# design.net
KiCad netlist of a schematic drawn in Altium Designer
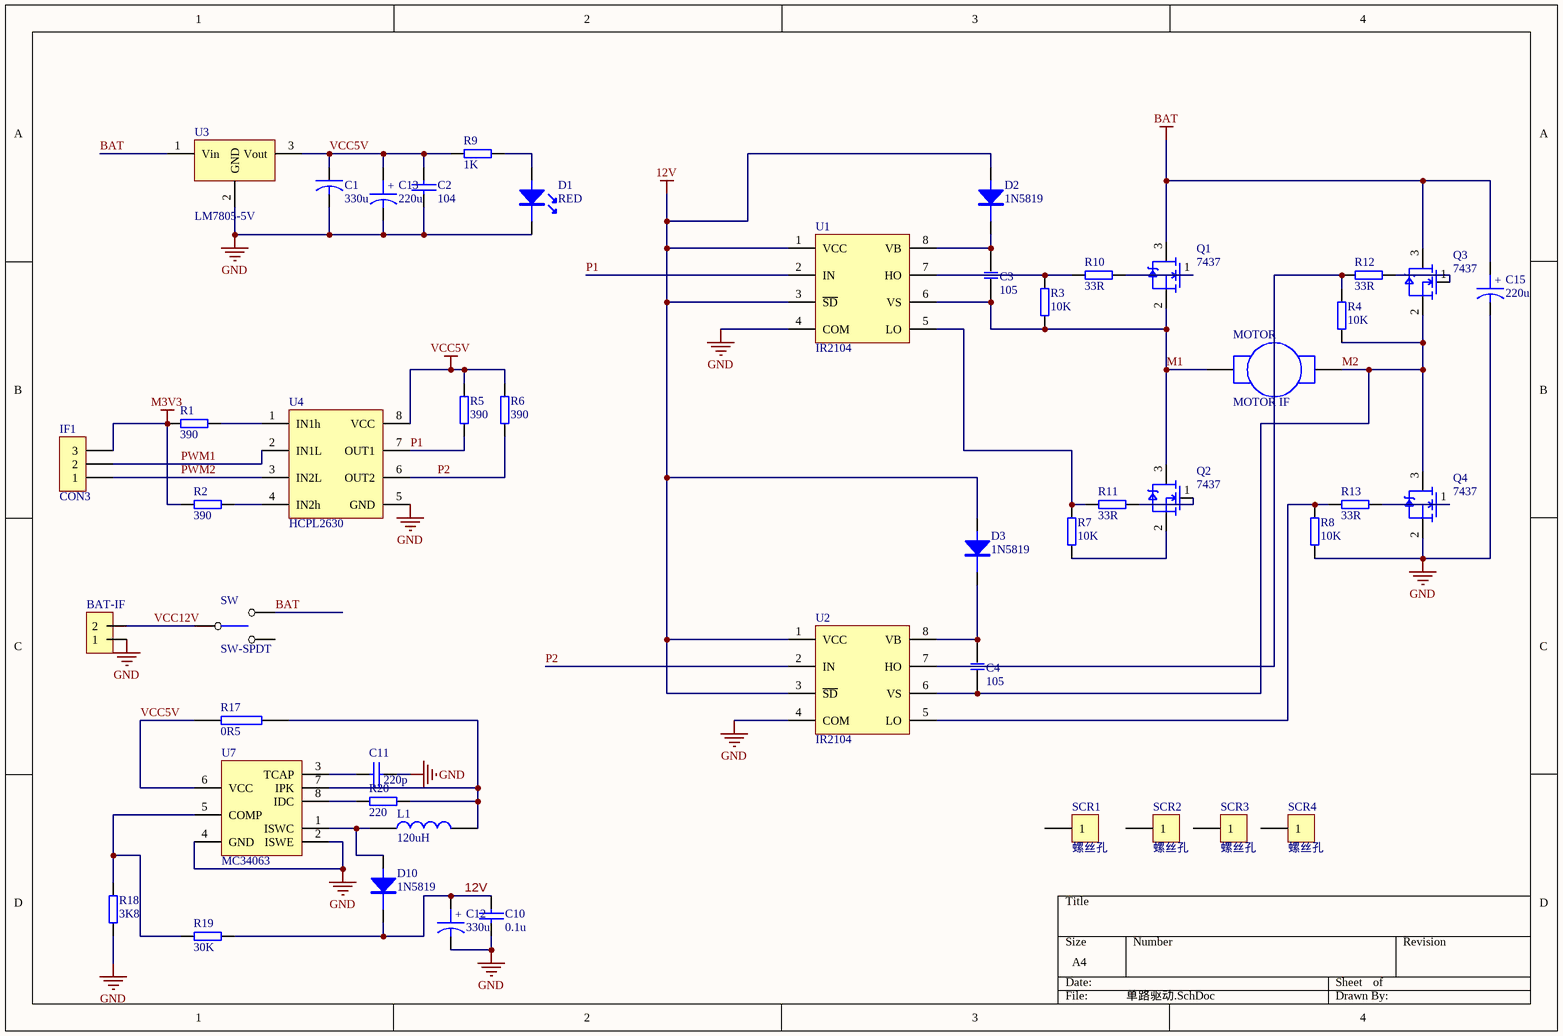
[diagram p0: 单路驱动.SchDoc]

(export (version "E")
  (design (tool "Eeschema 10.0.6"))
  (components
    (comp (ref "BAT-IF")
      (value "LQ_PIN2")
      (footprint "LQ_PIN2")
      (description "Jumper")
      (libsource (lib "LQ_MOSFET光隔全桥双路驱动加强版Vh") (part "LQ_PIN2"))
    )
    (comp (ref "C1")
      (value "330u")
      (footprint "LQ_7343D")
      (description "Capacitor")
      (libsource (lib "LQ_MOSFET光隔全桥双路驱动加强版Vh") (part "CAPACITOR"))
    )
    (comp (ref "C2")
      (value "104")
      (footprint "LQ_0603")
      (description "Capacitor")
      (libsource (lib "LQ_MOSFET光隔全桥双路驱动加强版Vh") (part "CAP"))
    )
    (comp (ref "C3")
      (value "105")
      (footprint "LQ_0603")
      (description "CAP")
      (libsource (lib "LQ_MOSFET光隔全桥双路驱动加强版Vh") (part "LQ_CAP"))
    )
    (comp (ref "C4")
      (value "105")
      (footprint "LQ_0603")
      (description "CAP")
      (libsource (lib "LQ_MOSFET光隔全桥双路驱动加强版Vh") (part "LQ_CAP"))
    )
    (comp (ref "C10")
      (value "0.1u")
      (footprint "LQ_0603")
      (description "Capacitor")
      (libsource (lib "LQ_MOSFET光隔全桥双路驱动加强版Vh") (part "CAP"))
    )
    (comp (ref "C11")
      (value "220p")
      (footprint "LQ_0603")
      (description "Capacitor")
      (libsource (lib "LQ_MOSFET光隔全桥双路驱动加强版Vh") (part "CAP"))
    )
    (comp (ref "C12")
      (value "330u")
      (footprint "LQ_220U16V")
      (description "10u")
      (libsource (lib "LQ_MOSFET光隔全桥双路驱动加强版Vh") (part "LQ_CAP_POL"))
    )
    (comp (ref "C13")
      (value "220u")
      (footprint "LQ_220U16V")
      (description "10u")
      (libsource (lib "LQ_MOSFET光隔全桥双路驱动加强版Vh") (part "LQ_CAP_POL"))
    )
    (comp (ref "C15")
      (value "220u")
      (footprint "LQ_220U16V")
      (description "10u")
      (libsource (lib "LQ_MOSFET光隔全桥双路驱动加强版Vh") (part "LQ_CAP_POL"))
    )
    (comp (ref "D1")
      (value "RED")
      (footprint "LQ_0603D")
      (libsource (lib "LQ_MOSFET光隔全桥双路驱动加强版Vh") (part "LQ_LED"))
    )
    (comp (ref "D2")
      (value "1N5819")
      (footprint "LQ_1206")
      (libsource (lib "LQ_MOSFET光隔全桥双路驱动加强版Vh") (part "LQ_DIODE"))
    )
    (comp (ref "D3")
      (value "1N5819")
      (footprint "LQ_1206")
      (libsource (lib "LQ_MOSFET光隔全桥双路驱动加强版Vh") (part "LQ_DIODE"))
    )
    (comp (ref "D10")
      (value "1N5819")
      (footprint "LQ_1206")
      (libsource (lib "LQ_MOSFET光隔全桥双路驱动加强版Vh") (part "LQ_DIODE"))
    )
    (comp (ref "IF1")
      (value "CON3")
      (footprint "Pin HDR1X3/2.54mm-S")
      (libsource (lib "LQ-TC264MB-V3") (part "Pin HDR1X3"))
    )
    (comp (ref "L1")
      (value "120uH")
      (footprint "LQ_1210")
      (libsource (lib "LQ_MOSFET光隔全桥双路驱动加强版Vh") (part "INDUCTOR"))
    )
    (comp (ref "MOTOR")
      (value "MOTOR IF")
      (footprint "LQ_PIN2")
      (libsource (lib "LQ_MOSFET光隔全桥双路驱动加强版Vh") (part "MOTOR AC"))
    )
    (comp (ref "Q1")
      (value "7437")
      (footprint "LQ_DPAK123")
      (description "BSS138N")
      (libsource (lib "LQ_MOSFET光隔全桥双路驱动加强版Vh") (part "BSS138N"))
    )
    (comp (ref "Q2")
      (value "7437")
      (footprint "LQ_DPAK123")
      (description "BSS138N")
      (libsource (lib "LQ_MOSFET光隔全桥双路驱动加强版Vh") (part "BSS138N"))
    )
    (comp (ref "Q3")
      (value "7437")
      (footprint "LQ_DPAK123")
      (description "BSS138N")
      (libsource (lib "LQ_MOSFET光隔全桥双路驱动加强版Vh") (part "BSS138N"))
    )
    (comp (ref "Q4")
      (value "7437")
      (footprint "LQ_DPAK123")
      (description "BSS138N")
      (libsource (lib "LQ_MOSFET光隔全桥双路驱动加强版Vh") (part "BSS138N"))
    )
    (comp (ref "R1")
      (value "390")
      (footprint "LQ_0603")
      (description "RES")
      (libsource (lib "LQ_MOSFET光隔全桥双路驱动加强版Vh") (part "LQ_RES"))
    )
    (comp (ref "R2")
      (value "390")
      (footprint "LQ_0603")
      (description "RES")
      (libsource (lib "LQ_MOSFET光隔全桥双路驱动加强版Vh") (part "LQ_RES"))
    )
    (comp (ref "R3")
      (value "10K")
      (footprint "LQ_0603")
      (description "RES")
      (libsource (lib "LQ_MOSFET光隔全桥双路驱动加强版Vh") (part "LQ_RES"))
    )
    (comp (ref "R4")
      (value "10K")
      (footprint "LQ_0603")
      (description "RES")
      (libsource (lib "LQ_MOSFET光隔全桥双路驱动加强版Vh") (part "LQ_RES"))
    )
    (comp (ref "R5")
      (value "390")
      (footprint "LQ_0603")
      (description "RES")
      (libsource (lib "LQ_MOSFET光隔全桥双路驱动加强版Vh") (part "LQ_RES"))
    )
    (comp (ref "R6")
      (value "390")
      (footprint "LQ_0603")
      (description "RES")
      (libsource (lib "LQ_MOSFET光隔全桥双路驱动加强版Vh") (part "LQ_RES"))
    )
    (comp (ref "R7")
      (value "10K")
      (footprint "LQ_0603")
      (description "RES")
      (libsource (lib "LQ_MOSFET光隔全桥双路驱动加强版Vh") (part "LQ_RES"))
    )
    (comp (ref "R8")
      (value "10K")
      (footprint "LQ_0603")
      (description "RES")
      (libsource (lib "LQ_MOSFET光隔全桥双路驱动加强版Vh") (part "LQ_RES"))
    )
    (comp (ref "R9")
      (value "1K")
      (footprint "LQ_0603")
      (description "RES")
      (libsource (lib "LQ_MOSFET光隔全桥双路驱动加强版Vh") (part "LQ_RES"))
    )
    (comp (ref "R10")
      (value "33R")
      (footprint "LQ_0603")
      (description "RES")
      (libsource (lib "LQ_MOSFET光隔全桥双路驱动加强版Vh") (part "LQ_RES"))
    )
    (comp (ref "R11")
      (value "33R")
      (footprint "LQ_0603")
      (description "RES")
      (libsource (lib "LQ_MOSFET光隔全桥双路驱动加强版Vh") (part "LQ_RES"))
    )
    (comp (ref "R12")
      (value "33R")
      (footprint "LQ_0603")
      (description "RES")
      (libsource (lib "LQ_MOSFET光隔全桥双路驱动加强版Vh") (part "LQ_RES"))
    )
    (comp (ref "R13")
      (value "33R")
      (footprint "LQ_0603")
      (description "RES")
      (libsource (lib "LQ_MOSFET光隔全桥双路驱动加强版Vh") (part "LQ_RES"))
    )
    (comp (ref "R17")
      (value "0R5")
      (footprint "LQ_0805")
      (libsource (lib "LQ_MOSFET光隔全桥双路驱动加强版Vh") (part "RES2"))
    )
    (comp (ref "R18")
      (value "3K8")
      (footprint "LQ_R0603")
      (description "RES")
      (libsource (lib "LQ-TC264MB-V3") (part "LQ_RES"))
    )
    (comp (ref "R19")
      (value "30K")
      (footprint "LQ_R0603")
      (description "RES")
      (libsource (lib "LQ-TC264MB-V3") (part "LQ_RES"))
    )
    (comp (ref "R20")
      (value "220")
      (footprint "LQ_0603")
      (description "RES")
      (libsource (lib "LQ_MOSFET光隔全桥双路驱动加强版Vh") (part "LQ_RES"))
    )
    (comp (ref "SCR1")
      (value "螺丝孔")
      (footprint "LQ_SCROW3&5mm")
      (description "Connector")
      (libsource (lib "LQ-TC264MB-V3") (part "CON1"))
    )
    (comp (ref "SCR2")
      (value "螺丝孔")
      (footprint "LQ_SCROW3&5mm")
      (description "Connector")
      (libsource (lib "LQ-TC264MB-V3") (part "CON1"))
    )
    (comp (ref "SCR3")
      (value "螺丝孔")
      (footprint "LQ_SCROW3&5mm")
      (description "Connector")
      (libsource (lib "LQ-TC264MB-V3") (part "CON1"))
    )
    (comp (ref "SCR4")
      (value "螺丝孔")
      (footprint "LQ_SCROW3&5mm")
      (description "Connector")
      (libsource (lib "LQ-TC264MB-V3") (part "CON1"))
    )
    (comp (ref "SW")
      (value "SW-SPDT")
      (footprint "LQ_SWSIP3")
      (libsource (lib "LQ_MOSFET光隔全桥双路驱动加强版Vh") (part "SW-SPDT"))
    )
    (comp (ref "U1")
      (value "IR2104")
      (footprint "SO-8")
      (libsource (lib "LQ_MOSFET光隔全桥双路驱动加强版Vh") (part "IR2104"))
    )
    (comp (ref "U2")
      (value "IR2104")
      (footprint "SO-8")
      (libsource (lib "LQ_MOSFET光隔全桥双路驱动加强版Vh") (part "IR2104"))
    )
    (comp (ref "U3")
      (value "LM7805-5V")
      (footprint "LQ_DPAK")
      (libsource (lib "LQ_MOSFET光隔全桥双路驱动加强版Vh") (part "LM7805"))
    )
    (comp (ref "U4")
      (value "HCPL2630")
      (footprint "DIP8")
      (description "6N137 2631")
      (libsource (lib "LQ_MOSFET光隔全桥双路驱动加强版Vh") (part "HCPL2630"))
    )
    (comp (ref "U7")
      (value "MC34063")
      (footprint "SO-8")
      (libsource (lib "LQ_MOSFET光隔全桥双路驱动加强版Vh") (part "MC34063"))
    )
  )
  (nets
    (net (code "1") (name "/M1") (class "Default")
      (node (ref "C3") (pin "2") (pinfunction "2_2") (pintype "passive"))
      (node (ref "MOTOR") (pin "1") (pinfunction "1_1") (pintype "passive"))
      (node (ref "Q1") (pin "2") (pinfunction "S_2") (pintype "passive"))
      (node (ref "Q2") (pin "3") (pinfunction "D_3") (pintype "passive"))
      (node (ref "R3") (pin "2") (pinfunction "2_2") (pintype "passive"))
      (node (ref "U1") (pin "6") (pinfunction "VS_6") (pintype "passive"))
    )
    (net (code "2") (name "/M2") (class "Default")
      (node (ref "C4") (pin "2") (pinfunction "2_2") (pintype "passive"))
      (node (ref "MOTOR") (pin "2") (pinfunction "2_2") (pintype "passive"))
      (node (ref "Q3") (pin "2") (pinfunction "S_2") (pintype "passive"))
      (node (ref "Q4") (pin "3") (pinfunction "D_3") (pintype "passive"))
      (node (ref "R4") (pin "2") (pinfunction "2_2") (pintype "passive"))
      (node (ref "U2") (pin "6") (pinfunction "VS_6") (pintype "passive"))
    )
    (net (code "3") (name "/P1") (class "Default")
      (node (ref "R5") (pin "2") (pinfunction "2_2") (pintype "passive"))
      (node (ref "U1") (pin "2") (pinfunction "IN_2") (pintype "passive"))
      (node (ref "U4") (pin "7") (pinfunction "OUT1_7") (pintype "passive"))
    )
    (net (code "4") (name "/P2") (class "Default")
      (node (ref "R6") (pin "2") (pinfunction "2_2") (pintype "passive"))
      (node (ref "U2") (pin "2") (pinfunction "IN_2") (pintype "passive"))
      (node (ref "U4") (pin "6") (pinfunction "OUT2_6") (pintype "passive"))
    )
    (net (code "5") (name "/PWM1") (class "Default")
      (node (ref "IF1") (pin "2") (pinfunction "2_2") (pintype "passive"))
      (node (ref "U4") (pin "2") (pinfunction "IN1L_2") (pintype "passive"))
    )
    (net (code "6") (name "/PWM2") (class "Default")
      (node (ref "IF1") (pin "1") (pinfunction "1_1") (pintype "passive"))
      (node (ref "U4") (pin "3") (pinfunction "IN2L_3") (pintype "passive"))
    )
    (net (code "7") (name "/VCC12V") (class "Default")
      (node (ref "BAT-IF") (pin "2") (pinfunction "2_2") (pintype "passive"))
      (node (ref "SW") (pin "1") (pinfunction "1_1") (pintype "passive"))
    )
    (net (code "8") (name "12V") (class "Default")
      (node (ref "C10") (pin "1") (pinfunction "1_1") (pintype "passive"))
      (node (ref "C12") (pin "1") (pinfunction "1_1") (pintype "passive"))
      (node (ref "D10") (pin "1") (pinfunction "1_1") (pintype "passive"))
      (node (ref "D2") (pin "2") (pinfunction "2_2") (pintype "passive"))
      (node (ref "D3") (pin "2") (pinfunction "2_2") (pintype "passive"))
      (node (ref "R19") (pin "2") (pinfunction "2_2") (pintype "passive"))
      (node (ref "U1") (pin "1") (pinfunction "VCC_1") (pintype "passive"))
      (node (ref "U1") (pin "3") (pinfunction "~{SD}_3") (pintype "passive"))
      (node (ref "U2") (pin "1") (pinfunction "VCC_1") (pintype "passive"))
      (node (ref "U2") (pin "3") (pinfunction "~{SD}_3") (pintype "passive"))
    )
    (net (code "9") (name "BAT") (class "Default")
      (node (ref "C15") (pin "1") (pinfunction "1_1") (pintype "passive"))
      (node (ref "Q1") (pin "3") (pinfunction "D_3") (pintype "passive"))
      (node (ref "Q3") (pin "3") (pinfunction "D_3") (pintype "passive"))
      (node (ref "SW") (pin "2") (pinfunction "2_2") (pintype "passive"))
      (node (ref "U3") (pin "1") (pinfunction "Vin_1") (pintype "passive"))
    )
    (net (code "10") (name "GND") (class "Default")
      (node (ref "BAT-IF") (pin "1") (pinfunction "1_1") (pintype "passive"))
      (node (ref "C1") (pin "2") (pinfunction "2_2") (pintype "passive"))
      (node (ref "C10") (pin "2") (pinfunction "2_2") (pintype "passive"))
      (node (ref "C11") (pin "2") (pinfunction "2_2") (pintype "passive"))
      (node (ref "C12") (pin "2") (pinfunction "2_2") (pintype "passive"))
      (node (ref "C13") (pin "2") (pinfunction "2_2") (pintype "passive"))
      (node (ref "C15") (pin "2") (pinfunction "2_2") (pintype "passive"))
      (node (ref "C2") (pin "2") (pinfunction "2_2") (pintype "passive"))
      (node (ref "D1") (pin "2") (pinfunction "2_2") (pintype "passive"))
      (node (ref "Q4") (pin "2") (pinfunction "S_2") (pintype "passive"))
      (node (ref "R18") (pin "2") (pinfunction "2_2") (pintype "passive"))
      (node (ref "R8") (pin "2") (pinfunction "2_2") (pintype "passive"))
      (node (ref "U1") (pin "4") (pinfunction "COM_4") (pintype "passive"))
      (node (ref "U2") (pin "4") (pinfunction "COM_4") (pintype "passive"))
      (node (ref "U3") (pin "2") (pinfunction "GND_2") (pintype "passive"))
      (node (ref "U4") (pin "5") (pinfunction "GND_5") (pintype "passive"))
      (node (ref "U7") (pin "2") (pinfunction "ISWE_2") (pintype "passive"))
      (node (ref "U7") (pin "4") (pinfunction "GND_4") (pintype "passive"))
    )
    (net (code "11") (name "M3V3") (class "Default")
      (node (ref "IF1") (pin "3") (pinfunction "3_3") (pintype "passive"))
      (node (ref "R1") (pin "1") (pinfunction "1_1") (pintype "passive"))
      (node (ref "R2") (pin "1") (pinfunction "1_1") (pintype "passive"))
    )
    (net (code "12") (name "Net-(D1-Pad1)") (class "Default")
      (node (ref "D1") (pin "1") (pinfunction "1_1") (pintype "passive"))
      (node (ref "R9") (pin "2") (pinfunction "2_2") (pintype "passive"))
    )
    (net (code "13") (name "Net-(Q1-G)") (class "Default")
      (node (ref "Q1") (pin "1") (pinfunction "G_1") (pintype "passive"))
      (node (ref "R10") (pin "2") (pinfunction "2_2") (pintype "passive"))
    )
    (net (code "14") (name "Net-(Q2-G)") (class "Default")
      (node (ref "Q2") (pin "1") (pinfunction "G_1") (pintype "passive"))
      (node (ref "R11") (pin "2") (pinfunction "2_2") (pintype "passive"))
    )
    (net (code "15") (name "Net-(Q2-S)") (class "Default")
      (node (ref "Q2") (pin "2") (pinfunction "S_2") (pintype "passive"))
      (node (ref "R7") (pin "2") (pinfunction "2_2") (pintype "passive"))
    )
    (net (code "16") (name "Net-(Q3-G)") (class "Default")
      (node (ref "Q3") (pin "1") (pinfunction "G_1") (pintype "passive"))
      (node (ref "R12") (pin "2") (pinfunction "2_2") (pintype "passive"))
    )
    (net (code "17") (name "Net-(Q4-G)") (class "Default")
      (node (ref "Q4") (pin "1") (pinfunction "G_1") (pintype "passive"))
      (node (ref "R13") (pin "2") (pinfunction "2_2") (pintype "passive"))
    )
    (net (code "18") (name "Net-(U1-HO)") (class "Default")
      (node (ref "R10") (pin "1") (pinfunction "1_1") (pintype "passive"))
      (node (ref "R3") (pin "1") (pinfunction "1_1") (pintype "passive"))
      (node (ref "U1") (pin "7") (pinfunction "HO_7") (pintype "passive"))
    )
    (net (code "19") (name "Net-(U1-LO)") (class "Default")
      (node (ref "R11") (pin "1") (pinfunction "1_1") (pintype "passive"))
      (node (ref "R7") (pin "1") (pinfunction "1_1") (pintype "passive"))
      (node (ref "U1") (pin "5") (pinfunction "LO_5") (pintype "passive"))
    )
    (net (code "20") (name "Net-(U1-VB)") (class "Default")
      (node (ref "C3") (pin "1") (pinfunction "1_1") (pintype "passive"))
      (node (ref "D2") (pin "1") (pinfunction "1_1") (pintype "passive"))
      (node (ref "U1") (pin "8") (pinfunction "VB_8") (pintype "passive"))
    )
    (net (code "21") (name "Net-(U2-HO)") (class "Default")
      (node (ref "R12") (pin "1") (pinfunction "1_1") (pintype "passive"))
      (node (ref "R4") (pin "1") (pinfunction "1_1") (pintype "passive"))
      (node (ref "U2") (pin "7") (pinfunction "HO_7") (pintype "passive"))
    )
    (net (code "22") (name "Net-(U2-LO)") (class "Default")
      (node (ref "R13") (pin "1") (pinfunction "1_1") (pintype "passive"))
      (node (ref "R8") (pin "1") (pinfunction "1_1") (pintype "passive"))
      (node (ref "U2") (pin "5") (pinfunction "LO_5") (pintype "passive"))
    )
    (net (code "23") (name "Net-(U2-VB)") (class "Default")
      (node (ref "C4") (pin "1") (pinfunction "1_1") (pintype "passive"))
      (node (ref "D3") (pin "1") (pinfunction "1_1") (pintype "passive"))
      (node (ref "U2") (pin "8") (pinfunction "VB_8") (pintype "passive"))
    )
    (net (code "24") (name "Net-(U4-IN1h)") (class "Default")
      (node (ref "R1") (pin "2") (pinfunction "2_2") (pintype "passive"))
      (node (ref "U4") (pin "1") (pinfunction "IN1h_1") (pintype "passive"))
    )
    (net (code "25") (name "Net-(U4-IN2h)") (class "Default")
      (node (ref "R2") (pin "2") (pinfunction "2_2") (pintype "passive"))
      (node (ref "U4") (pin "4") (pinfunction "IN2h_4") (pintype "passive"))
    )
    (net (code "26") (name "Net-(U7-COMP)") (class "Default")
      (node (ref "R18") (pin "1") (pinfunction "1_1") (pintype "passive"))
      (node (ref "R19") (pin "1") (pinfunction "1_1") (pintype "passive"))
      (node (ref "U7") (pin "5") (pinfunction "COMP_5") (pintype "passive"))
    )
    (net (code "27") (name "Net-(U7-IDC)") (class "Default")
      (node (ref "R20") (pin "1") (pinfunction "1_1") (pintype "passive"))
      (node (ref "U7") (pin "8") (pinfunction "IDC_8") (pintype "passive"))
    )
    (net (code "28") (name "Net-(U7-IPK)") (class "Default")
      (node (ref "L1") (pin "2") (pinfunction "2_2") (pintype "passive"))
      (node (ref "R17") (pin "2") (pinfunction "2_2") (pintype "passive"))
      (node (ref "R20") (pin "2") (pinfunction "2_2") (pintype "passive"))
      (node (ref "U7") (pin "7") (pinfunction "IPK_7") (pintype "passive"))
    )
    (net (code "29") (name "Net-(U7-ISWC)") (class "Default")
      (node (ref "D10") (pin "2") (pinfunction "2_2") (pintype "passive"))
      (node (ref "L1") (pin "1") (pinfunction "1_1") (pintype "passive"))
      (node (ref "U7") (pin "1") (pinfunction "ISWC_1") (pintype "passive"))
    )
    (net (code "30") (name "Net-(U7-TCAP)") (class "Default")
      (node (ref "C11") (pin "1") (pinfunction "1_1") (pintype "passive"))
      (node (ref "U7") (pin "3") (pinfunction "TCAP_3") (pintype "passive"))
    )
    (net (code "31") (name "VCC5V") (class "Default")
      (node (ref "C1") (pin "1") (pinfunction "1_1") (pintype "passive"))
      (node (ref "C13") (pin "1") (pinfunction "1_1") (pintype "passive"))
      (node (ref "C2") (pin "1") (pinfunction "1_1") (pintype "passive"))
      (node (ref "R17") (pin "1") (pinfunction "1_1") (pintype "passive"))
      (node (ref "R5") (pin "1") (pinfunction "1_1") (pintype "passive"))
      (node (ref "R6") (pin "1") (pinfunction "1_1") (pintype "passive"))
      (node (ref "R9") (pin "1") (pinfunction "1_1") (pintype "passive"))
      (node (ref "U3") (pin "3") (pinfunction "Vout_3") (pintype "passive"))
      (node (ref "U4") (pin "8") (pinfunction "VCC_8") (pintype "passive"))
      (node (ref "U7") (pin "6") (pinfunction "VCC_6") (pintype "passive"))
    )
    (net (code "32") (name "unconnected-(SCR1-Pad1)") (class "Default")
      (node (ref "SCR1") (pin "1") (pinfunction "1_1") (pintype "passive"))
    )
    (net (code "33") (name "unconnected-(SCR2-Pad1)") (class "Default")
      (node (ref "SCR2") (pin "1") (pinfunction "1_1") (pintype "passive"))
    )
    (net (code "34") (name "unconnected-(SCR3-Pad1)") (class "Default")
      (node (ref "SCR3") (pin "1") (pinfunction "1_1") (pintype "passive"))
    )
    (net (code "35") (name "unconnected-(SCR4-Pad1)") (class "Default")
      (node (ref "SCR4") (pin "1") (pinfunction "1_1") (pintype "passive"))
    )
    (net (code "36") (name "unconnected-(SW-Pad3)") (class "Default")
      (node (ref "SW") (pin "3") (pinfunction "3_3") (pintype "passive"))
    )
  )
)
